# STRWL-S01-V01-Master1.net
KiCad netlist of a schematic drawn in Altium Designer
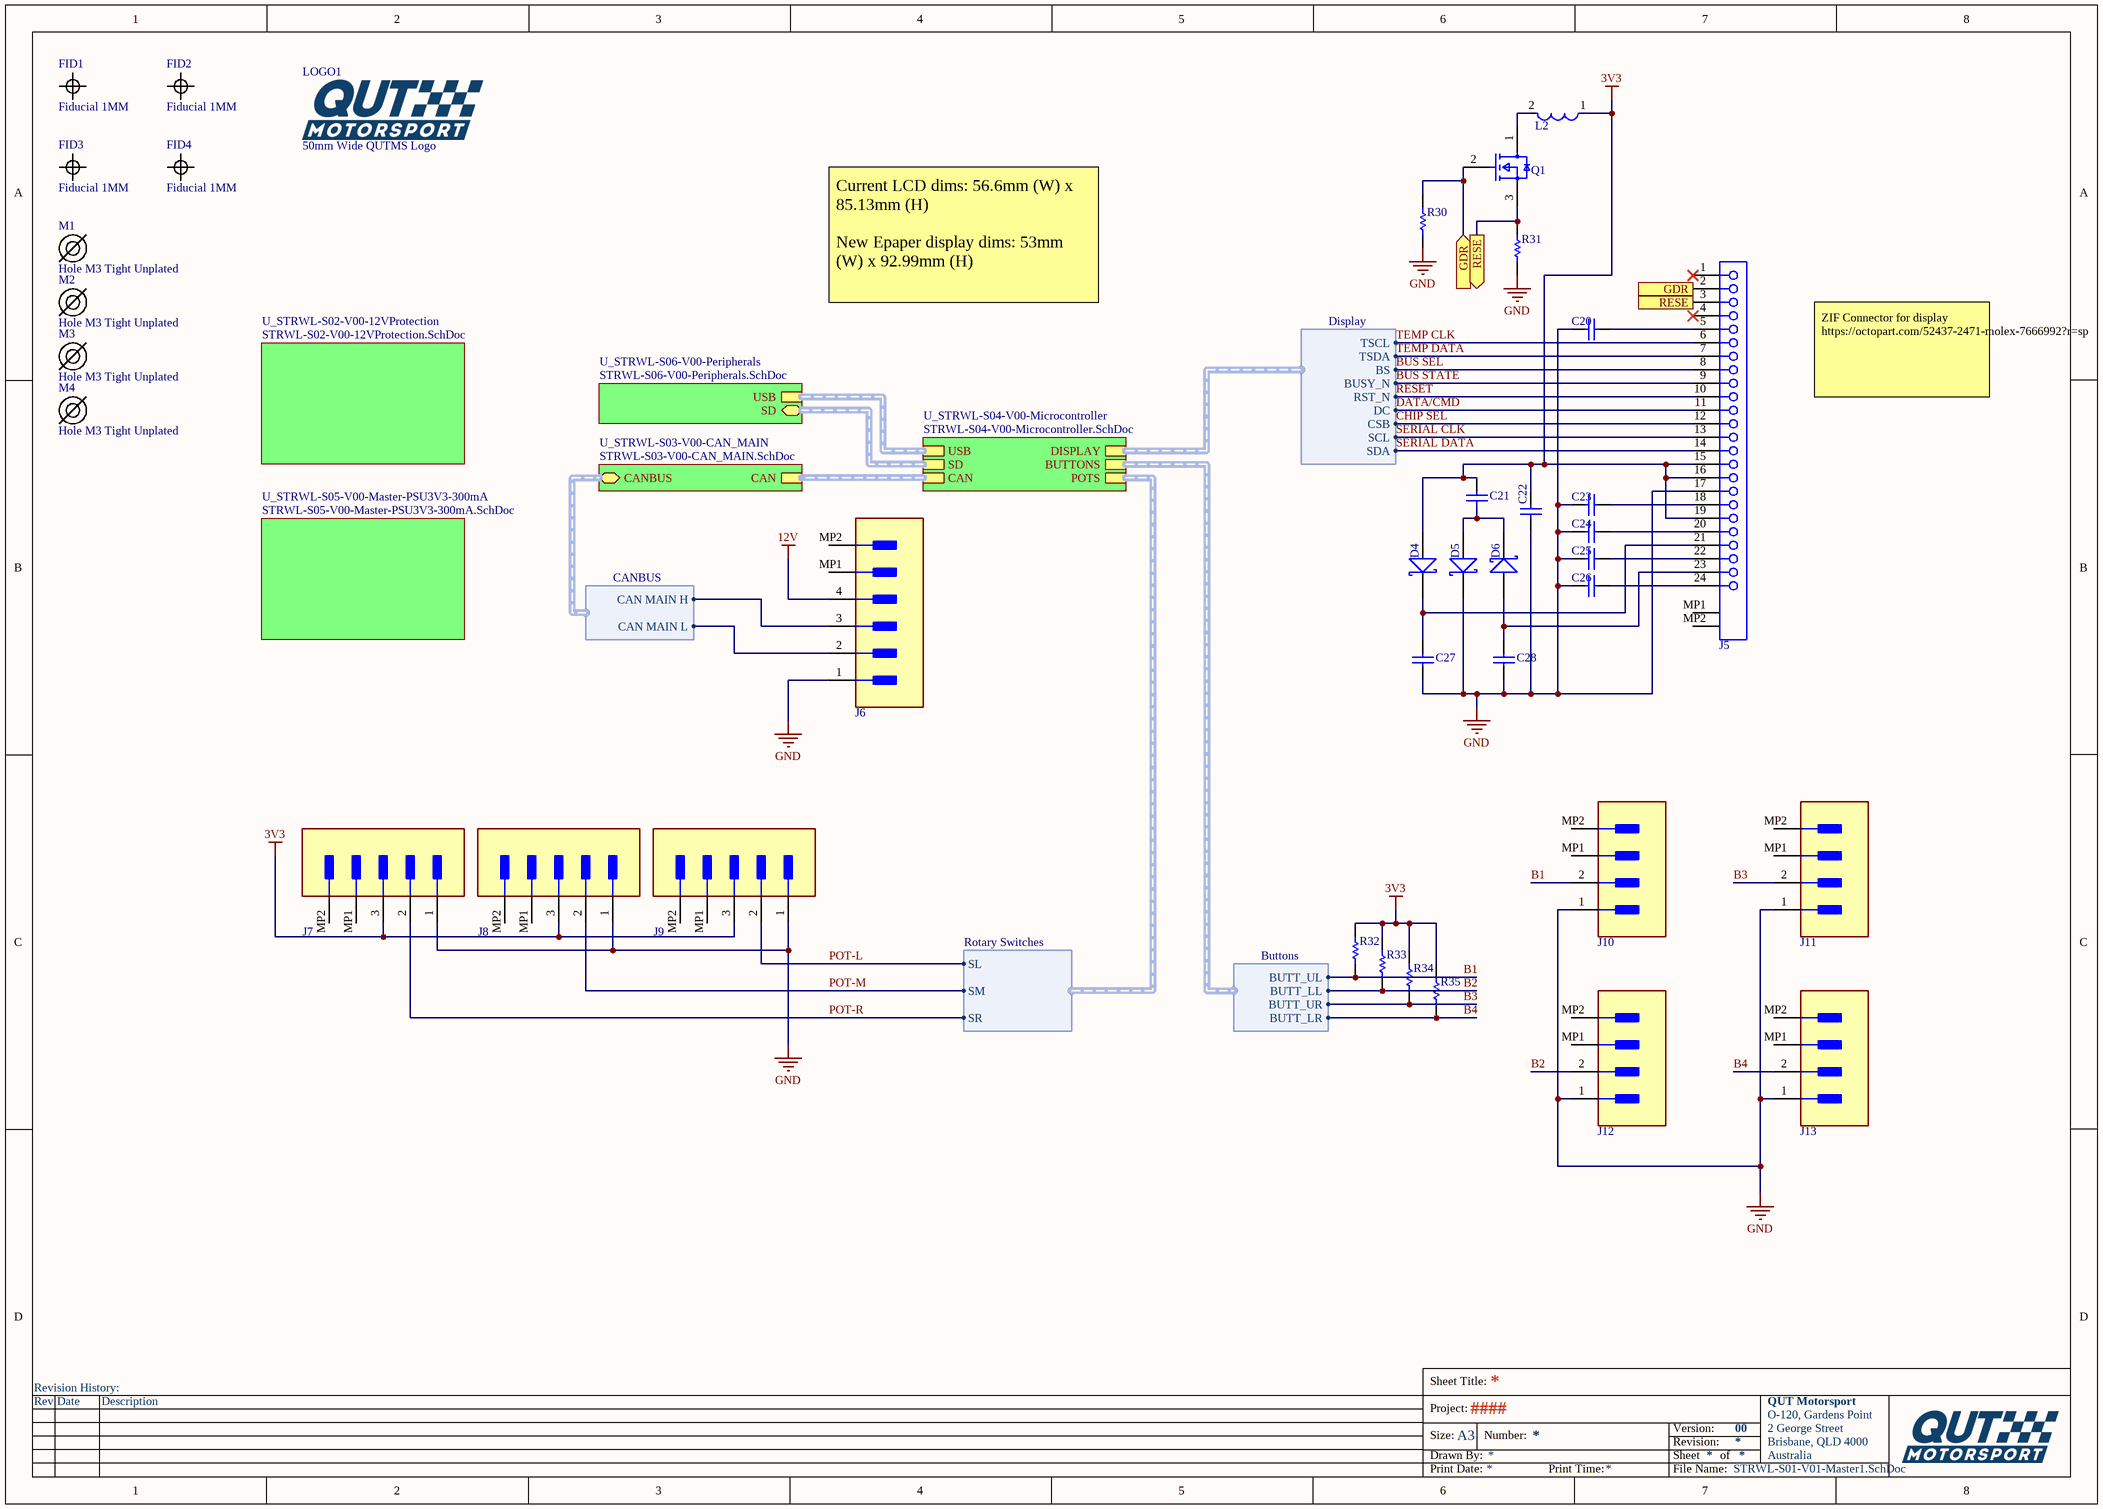
[diagram p0: STRWL-S01-V01-Master1.SchDoc]

(export (version "E")
  (design (tool "Eeschema 10.0.6"))
  (components
    (comp (ref "C20")
      (value "1uF 25V 5% X7R 0603")
      (footprint "Cap_Ceramic_0603")
      (description "Capacitor, Ceramic, SMD, 1uF, 25V, 5%, X7R, 0603")
      (libsource (lib "StandardCapacitors") (part "1uF 25V 5% X7R 0603"))
    )
    (comp (ref "C21")
      (value "4u7 50V 5% X7R 0603")
      (footprint "Cap_Ceramic_0603")
      (description "Capacitor, Ceramic, SMD, 4u7, 50V, 5%, X7R, 0603")
      (libsource (lib "StandardCapacitors") (part "4u7 50V 5% X7R 0603"))
    )
    (comp (ref "C22")
      (value "1uF 25V 5% X7R 0603")
      (footprint "Cap_Ceramic_0603")
      (description "Capacitor, Ceramic, SMD, 1uF, 25V, 5%, X7R, 0603")
      (libsource (lib "StandardCapacitors") (part "1uF 25V 5% X7R 0603"))
    )
    (comp (ref "C23")
      (value "1uF 25V 5% X7R 0603")
      (footprint "Cap_Ceramic_0603")
      (description "Capacitor, Ceramic, SMD, 1uF, 25V, 5%, X7R, 0603")
      (libsource (lib "StandardCapacitors") (part "1uF 25V 5% X7R 0603"))
    )
    (comp (ref "C24")
      (value "1uF 25V 5% X7R 0603")
      (footprint "Cap_Ceramic_0603")
      (description "Capacitor, Ceramic, SMD, 1uF, 25V, 5%, X7R, 0603")
      (libsource (lib "StandardCapacitors") (part "1uF 25V 5% X7R 0603"))
    )
    (comp (ref "C25")
      (value "1uF 25V 5% X7R 0603")
      (footprint "Cap_Ceramic_0603")
      (description "Capacitor, Ceramic, SMD, 1uF, 25V, 5%, X7R, 0603")
      (libsource (lib "StandardCapacitors") (part "1uF 25V 5% X7R 0603"))
    )
    (comp (ref "C26")
      (value "1uF 25V 5% X7R 0603")
      (footprint "Cap_Ceramic_0603")
      (description "Capacitor, Ceramic, SMD, 1uF, 25V, 5%, X7R, 0603")
      (libsource (lib "StandardCapacitors") (part "1uF 25V 5% X7R 0603"))
    )
    (comp (ref "C27")
      (value "1uF 25V 5% X7R 0603")
      (footprint "Cap_Ceramic_0603")
      (description "Capacitor, Ceramic, SMD, 1uF, 25V, 5%, X7R, 0603")
      (libsource (lib "StandardCapacitors") (part "1uF 25V 5% X7R 0603"))
    )
    (comp (ref "C28")
      (value "1uF 25V 5% X7R 0603")
      (footprint "Cap_Ceramic_0603")
      (description "Capacitor, Ceramic, SMD, 1uF, 25V, 5%, X7R, 0603")
      (libsource (lib "StandardCapacitors") (part "1uF 25V 5% X7R 0603"))
    )
    (comp (ref "D4")
      (value "STPS0530Z")
      (footprint "SOD123")
      (description "Diode, Schottky Barrier Rectifier, 30 V, 0.5 A, STPS0530Z")
      (libsource (lib "QUTMS_DiodeLibrary") (part "STPS0530Z"))
    )
    (comp (ref "D5")
      (value "STPS0530Z")
      (footprint "SOD123")
      (description "Diode, Schottky Barrier Rectifier, 30 V, 0.5 A, STPS0530Z")
      (libsource (lib "QUTMS_DiodeLibrary") (part "STPS0530Z"))
    )
    (comp (ref "D6")
      (value "STPS0530Z")
      (footprint "SOD123")
      (description "Diode, Schottky Barrier Rectifier, 30 V, 0.5 A, STPS0530Z")
      (libsource (lib "QUTMS_DiodeLibrary") (part "STPS0530Z"))
    )
    (comp (ref "FID1")
      (value "Fiducial 1MM")
      (footprint "FIDUCIAL 1MM")
      (libsource (lib "QUTMS-MCISOLibrary") (part "Fiducial 1MM"))
    )
    (comp (ref "FID2")
      (value "Fiducial 1MM")
      (footprint "FIDUCIAL 1MM")
      (libsource (lib "QUTMS-MCISOLibrary") (part "Fiducial 1MM"))
    )
    (comp (ref "FID3")
      (value "Fiducial 1MM")
      (footprint "FIDUCIAL 1MM")
      (libsource (lib "QUTMS-MCISOLibrary") (part "Fiducial 1MM"))
    )
    (comp (ref "FID4")
      (value "Fiducial 1MM")
      (footprint "FIDUCIAL 1MM")
      (libsource (lib "QUTMS-MCISOLibrary") (part "Fiducial 1MM"))
    )
    (comp (ref "J5")
      (value "52437-2471")
      (footprint "MOLX-52437-2471")
      (fields (field (name "MANUFACTURER") "Molex"))
      (libsource (lib "Molex_52437_2471") (part "52437-2471"))
    )
    (comp (ref "J6")
      (value "JST PH 4 Way VERT SMD")
      (footprint "JST 4P VERT SMD")
      (libsource (lib "QUTMS_JSTHeaderLibrary") (part "JST PH 4 Way VERT SMD"))
    )
    (comp (ref "J7")
      (value "JST PH 3 Way VERT SMD")
      (footprint "JST 3P VERT SMD")
      (libsource (lib "QUTMS_JSTHeaderLibrary") (part "JST PH 3 Way VERT SMD"))
    )
    (comp (ref "J8")
      (value "JST PH 3 Way VERT SMD")
      (footprint "JST 3P VERT SMD")
      (libsource (lib "QUTMS_JSTHeaderLibrary") (part "JST PH 3 Way VERT SMD"))
    )
    (comp (ref "J9")
      (value "JST PH 3 Way VERT SMD")
      (footprint "JST 3P VERT SMD")
      (libsource (lib "QUTMS_JSTHeaderLibrary") (part "JST PH 3 Way VERT SMD"))
    )
    (comp (ref "J10")
      (value "JSP PH 2 Way VERT SMD")
      (footprint "JST 2P VERT SMD")
      (fields (field (name "MANUFACTURER") "JST") (field (name "DIGIKEY PART NUMBER") "455-1734-1-ND"))
      (libsource (lib "QUTMS_JSTHeaderLibrary") (part "JSP PH 2 Way VERT SMD"))
    )
    (comp (ref "J11")
      (value "JSP PH 2 Way VERT SMD")
      (footprint "JST 2P VERT SMD")
      (fields (field (name "MANUFACTURER") "JST") (field (name "DIGIKEY PART NUMBER") "455-1734-1-ND"))
      (libsource (lib "QUTMS_JSTHeaderLibrary") (part "JSP PH 2 Way VERT SMD"))
    )
    (comp (ref "J12")
      (value "JSP PH 2 Way VERT SMD")
      (footprint "JST 2P VERT SMD")
      (fields (field (name "MANUFACTURER") "JST") (field (name "DIGIKEY PART NUMBER") "455-1734-1-ND"))
      (libsource (lib "QUTMS_JSTHeaderLibrary") (part "JSP PH 2 Way VERT SMD"))
    )
    (comp (ref "J13")
      (value "JSP PH 2 Way VERT SMD")
      (footprint "JST 2P VERT SMD")
      (fields (field (name "MANUFACTURER") "JST") (field (name "DIGIKEY PART NUMBER") "455-1734-1-ND"))
      (libsource (lib "QUTMS_JSTHeaderLibrary") (part "JSP PH 2 Way VERT SMD"))
    )
    (comp (ref "L2")
      (value "LQM21FN100M70L")
      (footprint "Murata_LQM21FN_70_IPC_C")
      (libsource (lib "QUTMS_InductorLibrary") (part "LQM21FN100M70L"))
    )
    (comp (ref "LOGO1")
      (value "50mm Wide QUTMS Logo")
      (footprint "QUTMS LOGO 50MM")
      (libsource (lib "QUTMS-MCISOLibrary") (part "QUTMS Logo 50mm"))
    )
    (comp (ref "M1")
      (value "Hole M3 Tight Unplated")
      (footprint "M3.2 UNPLATED")
      (description "M3.2 Hole, No Plating")
      (libsource (lib "QUTMS-MCISOLibrary") (part "Hole M3 Tight Unplated"))
    )
    (comp (ref "M2")
      (value "Hole M3 Tight Unplated")
      (footprint "M3.2 UNPLATED")
      (description "M3.2 Hole, No Plating")
      (libsource (lib "QUTMS-MCISOLibrary") (part "Hole M3 Tight Unplated"))
    )
    (comp (ref "M3")
      (value "Hole M3 Tight Unplated")
      (footprint "M3.2 UNPLATED")
      (description "M3.2 Hole, No Plating")
      (libsource (lib "QUTMS-MCISOLibrary") (part "Hole M3 Tight Unplated"))
    )
    (comp (ref "M4")
      (value "Hole M3 Tight Unplated")
      (footprint "M3.2 UNPLATED")
      (description "M3.2 Hole, No Plating")
      (libsource (lib "QUTMS-MCISOLibrary") (part "Hole M3 Tight Unplated"))
    )
    (comp (ref "Q1")
      (value "MOSFET N-CH 30V 4A SOT323")
      (footprint "Diodes_SOT323_0")
      (description "N-Channel 30V 4A (Ta) 770mW (Ta) Surface Mount SOT-323")
      (libsource (lib "QUTMS_DiodeLibrary") (part "DMN3065LW-13"))
    )
    (comp (ref "R30")
      (value "10k 1% 0603")
      (footprint "Res_ThinFilm_0603")
      (description "Resistor, SMD, 10k, 0.1W, 1%, 0603")
      (libsource (lib "StandardResistors") (part "10k 1% 0603"))
    )
    (comp (ref "R31")
      (value "0R47 5% 0603")
      (footprint "Res_ThinFilm_0603")
      (description "Resistor, SMD, 0R, 0.1W, 5%, 0603")
      (libsource (lib "StandardResistors") (part "0R47 5% 0603_1"))
    )
    (comp (ref "R32")
      (value "10k 5% 0603")
      (footprint "Res_ThinFilm_0603")
      (description "Resistor, SMD, 10k, 0.1W, 5%, 0603")
      (libsource (lib "StandardResistors") (part "10k 5% 0603"))
    )
    (comp (ref "R33")
      (value "10k 5% 0603")
      (footprint "Res_ThinFilm_0603")
      (description "Resistor, SMD, 10k, 0.1W, 5%, 0603")
      (libsource (lib "StandardResistors") (part "10k 5% 0603"))
    )
    (comp (ref "R34")
      (value "10k 5% 0603")
      (footprint "Res_ThinFilm_0603")
      (description "Resistor, SMD, 10k, 0.1W, 5%, 0603")
      (libsource (lib "StandardResistors") (part "10k 5% 0603"))
    )
    (comp (ref "R35")
      (value "10k 5% 0603")
      (footprint "Res_ThinFilm_0603")
      (description "Resistor, SMD, 10k, 0.1W, 5%, 0603")
      (libsource (lib "StandardResistors") (part "10k 5% 0603"))
    )
  )
  (nets
    (net (code "6") (name "/B1") (class "Default")
      (node (ref "J10") (pin "2") (pinfunction "2_2") (pintype "passive"))
      (node (ref "R32") (pin "2") (pinfunction "2_2") (pintype "passive"))
    )
    (net (code "7") (name "/B2") (class "Default")
      (node (ref "J12") (pin "2") (pinfunction "2_2") (pintype "passive"))
      (node (ref "R33") (pin "2") (pinfunction "2_2") (pintype "passive"))
    )
    (net (code "8") (name "/B3") (class "Default")
      (node (ref "J11") (pin "2") (pinfunction "2_2") (pintype "passive"))
      (node (ref "R34") (pin "1") (pinfunction "1_1") (pintype "passive"))
    )
    (net (code "9") (name "/B4") (class "Default")
      (node (ref "J13") (pin "2") (pinfunction "2_2") (pintype "passive"))
      (node (ref "R35") (pin "1") (pinfunction "1_1") (pintype "passive"))
    )
    (net (code "10") (name "/BUS SEL") (class "Default")
      (node (ref "J5") (pin "8") (pinfunction "8_8") (pintype "passive"))
    )
    (net (code "11") (name "/BUS STATE") (class "Default")
      (node (ref "J5") (pin "9") (pinfunction "9_9") (pintype "passive"))
    )
    (net (code "12") (name "/CAN MAIN H") (class "Default")
      (node (ref "J6") (pin "3") (pinfunction "3_3") (pintype "passive"))
    )
    (net (code "13") (name "/CAN MAIN L") (class "Default")
      (node (ref "J6") (pin "2") (pinfunction "2_2") (pintype "passive"))
    )
    (net (code "15") (name "/CHIP SEL") (class "Default")
      (node (ref "J5") (pin "12") (pinfunction "12_12") (pintype "passive"))
    )
    (net (code "16") (name "/DATA{slash}CMD") (class "Default")
      (node (ref "J5") (pin "11") (pinfunction "11_11") (pintype "passive"))
    )
    (net (code "17") (name "/GDR") (class "Default")
      (node (ref "J5") (pin "2") (pinfunction "2_2") (pintype "passive"))
      (node (ref "Q1") (pin "2") (pinfunction "G_2") (pintype "passive"))
      (node (ref "R30") (pin "1") (pinfunction "1_1") (pintype "passive"))
    )
    (net (code "18") (name "/POT-L") (class "Default")
      (node (ref "J9") (pin "2") (pinfunction "2_2") (pintype "passive"))
    )
    (net (code "19") (name "/POT-M") (class "Default")
      (node (ref "J8") (pin "2") (pinfunction "2_2") (pintype "passive"))
    )
    (net (code "20") (name "/POT-R") (class "Default")
      (node (ref "J7") (pin "2") (pinfunction "2_2") (pintype "passive"))
    )
    (net (code "21") (name "/RESE") (class "Default")
      (node (ref "J5") (pin "3") (pinfunction "3_3") (pintype "passive"))
      (node (ref "Q1") (pin "3") (pinfunction "S_3") (pintype "passive"))
      (node (ref "R31") (pin "2") (pinfunction "2_2") (pintype "passive"))
    )
    (net (code "22") (name "/RESET") (class "Default")
      (node (ref "J5") (pin "10") (pinfunction "10_10") (pintype "passive"))
    )
    (net (code "24") (name "/SERIAL CLK") (class "Default")
      (node (ref "J5") (pin "13") (pinfunction "13_13") (pintype "passive"))
    )
    (net (code "25") (name "/SERIAL DATA") (class "Default")
      (node (ref "J5") (pin "14") (pinfunction "14_14") (pintype "passive"))
    )
    (net (code "26") (name "/TEMP CLK") (class "Default")
      (node (ref "J5") (pin "6") (pinfunction "6_6") (pintype "passive"))
    )
    (net (code "27") (name "/TEMP DATA") (class "Default")
      (node (ref "J5") (pin "7") (pinfunction "7_7") (pintype "passive"))
    )
    (net (code "33") (name "3V3") (class "Default")
      (node (ref "C21") (pin "2") (pinfunction "2_2") (pintype "passive"))
      (node (ref "C22") (pin "2") (pinfunction "2_2") (pintype "passive"))
      (node (ref "D4") (pin "A") (pinfunction "A_A") (pintype "passive"))
      (node (ref "J5") (pin "15") (pinfunction "15_15") (pintype "passive"))
      (node (ref "J5") (pin "16") (pinfunction "16_16") (pintype "passive"))
      (node (ref "J5") (pin "19") (pinfunction "19_19") (pintype "passive"))
      (node (ref "J7") (pin "3") (pinfunction "3_3") (pintype "passive"))
      (node (ref "J8") (pin "3") (pinfunction "3_3") (pintype "passive"))
      (node (ref "J9") (pin "3") (pinfunction "3_3") (pintype "passive"))
      (node (ref "L2") (pin "1") (pinfunction "1_1") (pintype "passive"))
      (node (ref "R32") (pin "1") (pinfunction "1_1") (pintype "passive"))
      (node (ref "R33") (pin "1") (pinfunction "1_1") (pintype "passive"))
      (node (ref "R34") (pin "2") (pinfunction "2_2") (pintype "passive"))
      (node (ref "R35") (pin "2") (pinfunction "2_2") (pintype "passive"))
    )
    (net (code "34") (name "12V") (class "Default")
      (node (ref "J6") (pin "4") (pinfunction "4_4") (pintype "passive"))
    )
    (net (code "35") (name "GND") (class "Default")
      (node (ref "C20") (pin "1") (pinfunction "1_1") (pintype "passive"))
      (node (ref "C22") (pin "1") (pinfunction "1_1") (pintype "passive"))
      (node (ref "C23") (pin "1") (pinfunction "1_1") (pintype "passive"))
      (node (ref "C24") (pin "1") (pinfunction "1_1") (pintype "passive"))
      (node (ref "C25") (pin "1") (pinfunction "1_1") (pintype "passive"))
      (node (ref "C26") (pin "1") (pinfunction "1_1") (pintype "passive"))
      (node (ref "C27") (pin "1") (pinfunction "1_1") (pintype "passive"))
      (node (ref "C28") (pin "1") (pinfunction "1_1") (pintype "passive"))
      (node (ref "D5") (pin "K") (pinfunction "K_K") (pintype "passive"))
      (node (ref "J10") (pin "1") (pinfunction "1_1") (pintype "passive"))
      (node (ref "J11") (pin "1") (pinfunction "1_1") (pintype "passive"))
      (node (ref "J12") (pin "1") (pinfunction "1_1") (pintype "passive"))
      (node (ref "J13") (pin "1") (pinfunction "1_1") (pintype "passive"))
      (node (ref "J5") (pin "17") (pinfunction "17_17") (pintype "passive"))
      (node (ref "J6") (pin "1") (pinfunction "1_1") (pintype "passive"))
      (node (ref "J7") (pin "1") (pinfunction "1_1") (pintype "passive"))
      (node (ref "J8") (pin "1") (pinfunction "1_1") (pintype "passive"))
      (node (ref "J9") (pin "1") (pinfunction "1_1") (pintype "passive"))
      (node (ref "R30") (pin "2") (pinfunction "2_2") (pintype "passive"))
      (node (ref "R31") (pin "1") (pinfunction "1_1") (pintype "passive"))
    )
    (net (code "36") (name "Net-(C20-Pad2)") (class "Default")
      (node (ref "C20") (pin "2") (pinfunction "2_2") (pintype "passive"))
      (node (ref "J5") (pin "5") (pinfunction "5_5") (pintype "passive"))
    )
    (net (code "37") (name "Net-(C21-Pad1)") (class "Default")
      (node (ref "C21") (pin "1") (pinfunction "1_1") (pintype "passive"))
      (node (ref "D5") (pin "A") (pinfunction "A_A") (pintype "passive"))
      (node (ref "D6") (pin "K") (pinfunction "K_K") (pintype "passive"))
    )
    (net (code "38") (name "Net-(C23-Pad2)") (class "Default")
      (node (ref "C23") (pin "2") (pinfunction "2_2") (pintype "passive"))
      (node (ref "J5") (pin "18") (pinfunction "18_18") (pintype "passive"))
    )
    (net (code "39") (name "Net-(C24-Pad2)") (class "Default")
      (node (ref "C24") (pin "2") (pinfunction "2_2") (pintype "passive"))
      (node (ref "J5") (pin "20") (pinfunction "20_20") (pintype "passive"))
    )
    (net (code "40") (name "Net-(C25-Pad2)") (class "Default")
      (node (ref "C25") (pin "2") (pinfunction "2_2") (pintype "passive"))
      (node (ref "J5") (pin "22") (pinfunction "22_22") (pintype "passive"))
    )
    (net (code "41") (name "Net-(C26-Pad2)") (class "Default")
      (node (ref "C26") (pin "2") (pinfunction "2_2") (pintype "passive"))
      (node (ref "J5") (pin "24") (pinfunction "24_24") (pintype "passive"))
    )
    (net (code "42") (name "Net-(C27-Pad2)") (class "Default")
      (node (ref "C27") (pin "2") (pinfunction "2_2") (pintype "passive"))
      (node (ref "D4") (pin "K") (pinfunction "K_K") (pintype "passive"))
      (node (ref "J5") (pin "21") (pinfunction "21_21") (pintype "passive"))
    )
    (net (code "43") (name "Net-(C28-Pad2)") (class "Default")
      (node (ref "C28") (pin "2") (pinfunction "2_2") (pintype "passive"))
      (node (ref "D6") (pin "A") (pinfunction "A_A") (pintype "passive"))
      (node (ref "J5") (pin "23") (pinfunction "23_23") (pintype "passive"))
    )
    (net (code "44") (name "Net-(Q1-D)") (class "Default")
      (node (ref "L2") (pin "2") (pinfunction "2_2") (pintype "passive"))
      (node (ref "Q1") (pin "1") (pinfunction "D_1") (pintype "passive"))
    )
    (net (code "45") (name "unconnected-(J5-Pad1)") (class "Default")
      (node (ref "J5") (pin "1") (pinfunction "1_1") (pintype "passive+no_connect"))
    )
    (net (code "46") (name "unconnected-(J5-Pad4)") (class "Default")
      (node (ref "J5") (pin "4") (pinfunction "4_4") (pintype "passive+no_connect"))
    )
    (net (code "47") (name "unconnected-(J5-PadMP1)") (class "Default")
      (node (ref "J5") (pin "MP1") (pinfunction "MP1_MP1") (pintype "passive"))
    )
    (net (code "48") (name "unconnected-(J5-PadMP2)") (class "Default")
      (node (ref "J5") (pin "MP2") (pinfunction "MP2_MP2") (pintype "passive"))
    )
    (net (code "49") (name "unconnected-(J6-MNT_1-PadMP1)") (class "Default")
      (node (ref "J6") (pin "MP1") (pinfunction "MNT_1_MP1") (pintype "passive"))
    )
    (net (code "50") (name "unconnected-(J6-MNT_2-PadMP2)") (class "Default")
      (node (ref "J6") (pin "MP2") (pinfunction "MNT_2_MP2") (pintype "passive"))
    )
    (net (code "51") (name "unconnected-(J7-MNT_1-PadMP1)") (class "Default")
      (node (ref "J7") (pin "MP1") (pinfunction "MNT_1_MP1") (pintype "passive"))
    )
    (net (code "52") (name "unconnected-(J7-MNT_2-PadMP2)") (class "Default")
      (node (ref "J7") (pin "MP2") (pinfunction "MNT_2_MP2") (pintype "passive"))
    )
    (net (code "53") (name "unconnected-(J8-MNT_1-PadMP1)") (class "Default")
      (node (ref "J8") (pin "MP1") (pinfunction "MNT_1_MP1") (pintype "passive"))
    )
    (net (code "54") (name "unconnected-(J8-MNT_2-PadMP2)") (class "Default")
      (node (ref "J8") (pin "MP2") (pinfunction "MNT_2_MP2") (pintype "passive"))
    )
    (net (code "55") (name "unconnected-(J9-MNT_1-PadMP1)") (class "Default")
      (node (ref "J9") (pin "MP1") (pinfunction "MNT_1_MP1") (pintype "passive"))
    )
    (net (code "56") (name "unconnected-(J9-MNT_2-PadMP2)") (class "Default")
      (node (ref "J9") (pin "MP2") (pinfunction "MNT_2_MP2") (pintype "passive"))
    )
    (net (code "57") (name "unconnected-(J10-MNT_1-PadMP1)") (class "Default")
      (node (ref "J10") (pin "MP1") (pinfunction "MNT_1_MP1") (pintype "passive"))
    )
    (net (code "58") (name "unconnected-(J10-MNT_2-PadMP2)") (class "Default")
      (node (ref "J10") (pin "MP2") (pinfunction "MNT_2_MP2") (pintype "passive"))
    )
    (net (code "59") (name "unconnected-(J11-MNT_1-PadMP1)") (class "Default")
      (node (ref "J11") (pin "MP1") (pinfunction "MNT_1_MP1") (pintype "passive"))
    )
    (net (code "60") (name "unconnected-(J11-MNT_2-PadMP2)") (class "Default")
      (node (ref "J11") (pin "MP2") (pinfunction "MNT_2_MP2") (pintype "passive"))
    )
    (net (code "61") (name "unconnected-(J12-MNT_1-PadMP1)") (class "Default")
      (node (ref "J12") (pin "MP1") (pinfunction "MNT_1_MP1") (pintype "passive"))
    )
    (net (code "62") (name "unconnected-(J12-MNT_2-PadMP2)") (class "Default")
      (node (ref "J12") (pin "MP2") (pinfunction "MNT_2_MP2") (pintype "passive"))
    )
    (net (code "63") (name "unconnected-(J13-MNT_1-PadMP1)") (class "Default")
      (node (ref "J13") (pin "MP1") (pinfunction "MNT_1_MP1") (pintype "passive"))
    )
    (net (code "64") (name "unconnected-(J13-MNT_2-PadMP2)") (class "Default")
      (node (ref "J13") (pin "MP2") (pinfunction "MNT_2_MP2") (pintype "passive"))
    )
  )
)
